# schema.net
KiCad netlist of a schematic drawn in EAGLE
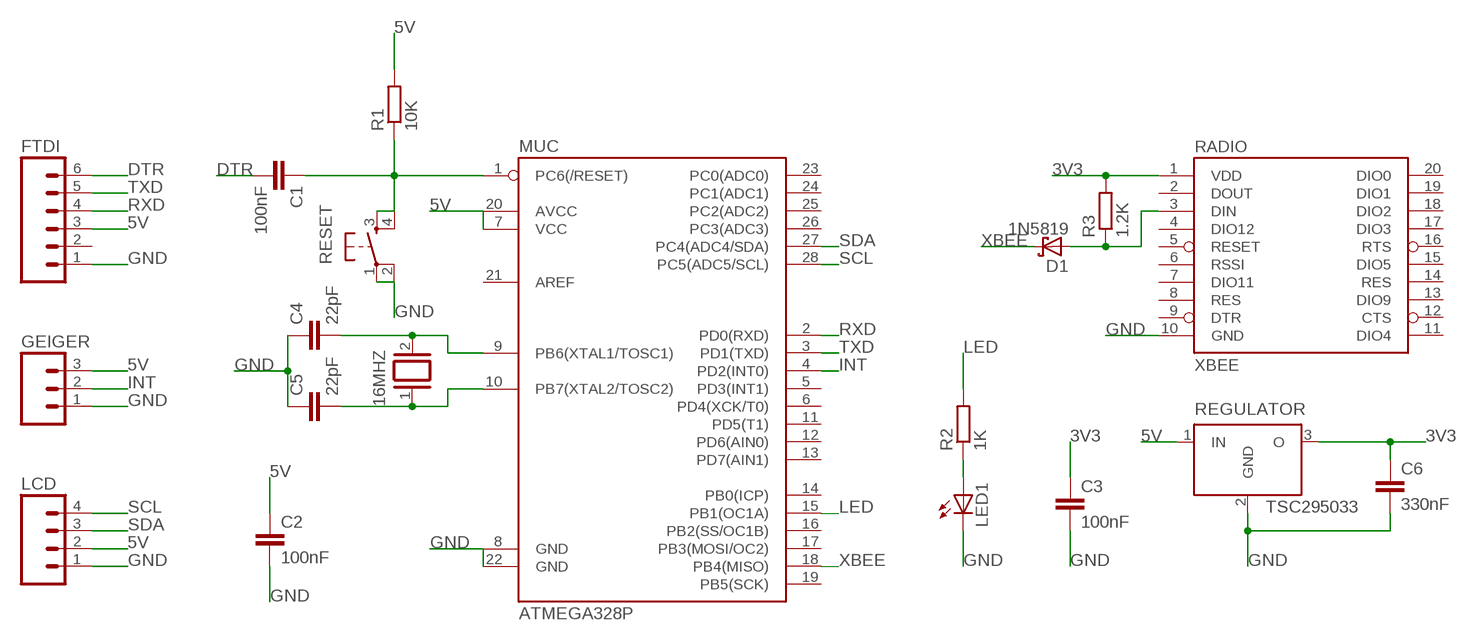
[diagram p0: schematic, sheet 1]

(export (version "E")
  (design (tool "Eeschema 10.0.6"))
  (components
    (comp (ref "16MHZ")
      (value "XTAL/S")
      (footprint "eagle-import:QS")
      (libsource (lib "eagle-import") (part "XTAL/S"))
    )
    (comp (ref "C1")
      (value "100nF")
      (footprint "eagle-import:C025-025X050")
      (libsource (lib "eagle-import") (part "C-EU025-025X050"))
    )
    (comp (ref "C2")
      (value "100nF")
      (footprint "eagle-import:C025-025X050")
      (libsource (lib "eagle-import") (part "C-EU025-025X050"))
    )
    (comp (ref "C3")
      (value "100nF")
      (footprint "eagle-import:C025-025X050")
      (libsource (lib "eagle-import") (part "C-EU025-025X050"))
    )
    (comp (ref "C4")
      (value "22pF")
      (footprint "eagle-import:C025-025X050")
      (libsource (lib "eagle-import") (part "C-EU025-025X050"))
    )
    (comp (ref "C5")
      (value "22pF")
      (footprint "eagle-import:C025-025X050")
      (libsource (lib "eagle-import") (part "C-EU025-025X050"))
    )
    (comp (ref "C6")
      (value "330nF")
      (footprint "eagle-import:C025-025X050")
      (libsource (lib "eagle-import") (part "C-EU025-025X050"))
    )
    (comp (ref "D1")
      (value "1N5819")
      (footprint "eagle-import:DO41-7.6")
      (libsource (lib "eagle-import") (part "1N5819-B"))
    )
    (comp (ref "FTDI")
      (value "M06SIP")
      (footprint "eagle-import:1X06")
      (libsource (lib "eagle-import") (part "M06SIP"))
    )
    (comp (ref "GEIGER")
      (value "M03PTH")
      (footprint "eagle-import:1X03")
      (libsource (lib "eagle-import") (part "M03PTH"))
    )
    (comp (ref "LCD")
      (value "M04PTH")
      (footprint "eagle-import:1X04")
      (libsource (lib "eagle-import") (part "M04PTH"))
    )
    (comp (ref "LED1")
      (value "LED3MM")
      (footprint "eagle-import:LED3MM")
      (libsource (lib "eagle-import") (part "LED3MM"))
    )
    (comp (ref "MUC")
      (value "ATMEGA328P")
      (footprint "eagle-import:DIL28-3")
      (libsource (lib "eagle-import") (part "ATMEGA328P_PDIP"))
    )
    (comp (ref "R1")
      (value "10K")
      (footprint "eagle-import:0207_10")
      (libsource (lib "eagle-import") (part "R-EU_0207/10"))
    )
    (comp (ref "R2")
      (value "1K")
      (footprint "eagle-import:0207_10")
      (libsource (lib "eagle-import") (part "R-EU_0207/10"))
    )
    (comp (ref "R3")
      (value "1.2K")
      (footprint "eagle-import:0207_10")
      (libsource (lib "eagle-import") (part "R-EU_0207/10"))
    )
    (comp (ref "RADIO")
      (value "XBEE")
      (footprint "eagle-import:XBEE-1")
      (libsource (lib "eagle-import") (part "XBEE-1B1"))
    )
    (comp (ref "REGULATOR")
      (value "TSC295033")
      (footprint "eagle-import:TO92")
      (fields (field (name "MF") "NATIONAL SEMICONDUCTOR") (field (name "MPN") "LP2950CZ-5.0/NOPB"))
      (libsource (lib "eagle-import") (part "LP2950Z"))
    )
    (comp (ref "RESET")
      (value "TAC_SWITCHPTH")
      (footprint "eagle-import:TACTILE-PTH")
      (libsource (lib "eagle-import") (part "TAC_SWITCHPTH"))
    )
  )
  (nets
    (net (code "1") (name "/3V3") (class "Default")
      (node (ref "C3") (pin "1") (pinfunction "1_1") (pintype "passive"))
      (node (ref "C6") (pin "1") (pinfunction "1_1") (pintype "passive"))
      (node (ref "R3") (pin "2") (pinfunction "2_2") (pintype "passive"))
      (node (ref "RADIO") (pin "1") (pinfunction "VDD_1") (pintype "power_in"))
      (node (ref "REGULATOR") (pin "3") (pinfunction "O_3") (pintype "output"))
    )
    (net (code "2") (name "/5V") (class "Default")
      (node (ref "C2") (pin "1") (pinfunction "1_1") (pintype "passive"))
      (node (ref "FTDI") (pin "3") (pinfunction "3_3") (pintype "passive"))
      (node (ref "GEIGER") (pin "3") (pinfunction "3_3") (pintype "passive"))
      (node (ref "LCD") (pin "2") (pinfunction "2_2") (pintype "passive"))
      (node (ref "MUC") (pin "20") (pinfunction "AVCC_20") (pintype "bidirectional"))
      (node (ref "MUC") (pin "7") (pinfunction "VCC_7") (pintype "bidirectional"))
      (node (ref "R1") (pin "2") (pinfunction "2_2") (pintype "passive"))
      (node (ref "REGULATOR") (pin "1") (pinfunction "IN_1") (pintype "input"))
    )
    (net (code "3") (name "/DTR") (class "Default")
      (node (ref "C1") (pin "2") (pinfunction "2_2") (pintype "passive"))
      (node (ref "FTDI") (pin "6") (pinfunction "6_6") (pintype "passive"))
    )
    (net (code "4") (name "/GND") (class "Default")
      (node (ref "C2") (pin "2") (pinfunction "2_2") (pintype "passive"))
      (node (ref "C3") (pin "2") (pinfunction "2_2") (pintype "passive"))
      (node (ref "C4") (pin "1") (pinfunction "1_1") (pintype "passive"))
      (node (ref "C5") (pin "1") (pinfunction "1_1") (pintype "passive"))
      (node (ref "C6") (pin "2") (pinfunction "2_2") (pintype "passive"))
      (node (ref "FTDI") (pin "1") (pinfunction "1_1") (pintype "passive"))
      (node (ref "GEIGER") (pin "1") (pinfunction "1_1") (pintype "passive"))
      (node (ref "LCD") (pin "1") (pinfunction "1_1") (pintype "passive"))
      (node (ref "LED1") (pin "K") (pinfunction "C_K") (pintype "passive"))
      (node (ref "MUC") (pin "22") (pinfunction "GND_22") (pintype "bidirectional"))
      (node (ref "MUC") (pin "8") (pinfunction "GND_8") (pintype "bidirectional"))
      (node (ref "RADIO") (pin "10") (pinfunction "GND_10") (pintype "power_in"))
      (node (ref "REGULATOR") (pin "2") (pinfunction "GND_2") (pintype "power_in"))
      (node (ref "RESET") (pin "1") (pinfunction "1_1") (pintype "passive"))
      (node (ref "RESET") (pin "2") (pinfunction "2_2") (pintype "passive"))
    )
    (net (code "5") (name "/INT") (class "Default")
      (node (ref "GEIGER") (pin "2") (pinfunction "2_2") (pintype "passive"))
      (node (ref "MUC") (pin "4") (pinfunction "PD2(INT0)_4") (pintype "bidirectional"))
    )
    (net (code "6") (name "/LED") (class "Default")
      (node (ref "MUC") (pin "15") (pinfunction "PB1(OC1A)_15") (pintype "bidirectional"))
      (node (ref "R2") (pin "2") (pinfunction "2_2") (pintype "passive"))
    )
    (net (code "7") (name "/RXD") (class "Default")
      (node (ref "FTDI") (pin "4") (pinfunction "4_4") (pintype "passive"))
      (node (ref "MUC") (pin "2") (pinfunction "PD0(RXD)_2") (pintype "bidirectional"))
    )
    (net (code "8") (name "/SCL") (class "Default")
      (node (ref "LCD") (pin "4") (pinfunction "4_4") (pintype "passive"))
      (node (ref "MUC") (pin "28") (pinfunction "PC5(ADC5/SCL)_28") (pintype "bidirectional"))
    )
    (net (code "9") (name "/SDA") (class "Default")
      (node (ref "LCD") (pin "3") (pinfunction "3_3") (pintype "passive"))
      (node (ref "MUC") (pin "27") (pinfunction "PC4(ADC4/SDA)_27") (pintype "bidirectional"))
    )
    (net (code "10") (name "/TXD") (class "Default")
      (node (ref "FTDI") (pin "5") (pinfunction "5_5") (pintype "passive"))
      (node (ref "MUC") (pin "3") (pinfunction "PD1(TXD)_3") (pintype "bidirectional"))
    )
    (net (code "11") (name "/XBEE") (class "Default")
      (node (ref "D1") (pin "C") (pinfunction "C_C") (pintype "passive"))
      (node (ref "MUC") (pin "18") (pinfunction "PB4(MISO)_18") (pintype "bidirectional"))
    )
    (net (code "12") (name "Net-(LED1-PadA)") (class "Default")
      (node (ref "LED1") (pin "A") (pinfunction "A_A") (pintype "passive"))
      (node (ref "R2") (pin "1") (pinfunction "1_1") (pintype "passive"))
    )
    (net (code "13") (name "Net-(MUC-PB6(XTAL1{slash}TOSC1))") (class "Default")
      (node (ref "16MHZ") (pin "2") (pinfunction "2_2") (pintype "passive"))
      (node (ref "C4") (pin "2") (pinfunction "2_2") (pintype "passive"))
      (node (ref "MUC") (pin "9") (pinfunction "PB6(XTAL1/TOSC1)_9") (pintype "bidirectional"))
    )
    (net (code "14") (name "Net-(MUC-PB7(XTAL2{slash}TOSC2))") (class "Default")
      (node (ref "16MHZ") (pin "1") (pinfunction "1_1") (pintype "passive"))
      (node (ref "C5") (pin "2") (pinfunction "2_2") (pintype "passive"))
      (node (ref "MUC") (pin "10") (pinfunction "PB7(XTAL2/TOSC2)_10") (pintype "bidirectional"))
    )
    (net (code "15") (name "Net-(MUC-PC6({slash}RESET))") (class "Default")
      (node (ref "C1") (pin "1") (pinfunction "1_1") (pintype "passive"))
      (node (ref "MUC") (pin "1") (pinfunction "PC6(/RESET)_1") (pintype "bidirectional"))
      (node (ref "R1") (pin "1") (pinfunction "1_1") (pintype "passive"))
      (node (ref "RESET") (pin "3") (pinfunction "3_3") (pintype "passive"))
      (node (ref "RESET") (pin "4") (pinfunction "4_4") (pintype "passive"))
    )
    (net (code "16") (name "Net-(RADIO-DIN)") (class "Default")
      (node (ref "D1") (pin "A") (pinfunction "A_A") (pintype "passive"))
      (node (ref "R3") (pin "1") (pinfunction "1_1") (pintype "passive"))
      (node (ref "RADIO") (pin "3") (pinfunction "DIN_3") (pintype "input"))
    )
    (net (code "17") (name "unconnected-(FTDI-Pad2)") (class "Default")
      (node (ref "FTDI") (pin "2") (pinfunction "2_2") (pintype "passive"))
    )
    (net (code "18") (name "unconnected-(MUC-AREF-Pad21)") (class "Default")
      (node (ref "MUC") (pin "21") (pinfunction "AREF_21") (pintype "bidirectional"))
    )
    (net (code "19") (name "unconnected-(MUC-PB0(ICP)-Pad14)") (class "Default")
      (node (ref "MUC") (pin "14") (pinfunction "PB0(ICP)_14") (pintype "bidirectional"))
    )
    (net (code "20") (name "unconnected-(MUC-PB2(SS{slash}OC1B)-Pad16)") (class "Default")
      (node (ref "MUC") (pin "16") (pinfunction "PB2(SS/OC1B)_16") (pintype "bidirectional"))
    )
    (net (code "21") (name "unconnected-(MUC-PB3(MOSI{slash}OC2)-Pad17)") (class "Default")
      (node (ref "MUC") (pin "17") (pinfunction "PB3(MOSI/OC2)_17") (pintype "bidirectional"))
    )
    (net (code "22") (name "unconnected-(MUC-PB5(SCK)-Pad19)") (class "Default")
      (node (ref "MUC") (pin "19") (pinfunction "PB5(SCK)_19") (pintype "bidirectional"))
    )
    (net (code "23") (name "unconnected-(MUC-PC0(ADC0)-Pad23)") (class "Default")
      (node (ref "MUC") (pin "23") (pinfunction "PC0(ADC0)_23") (pintype "bidirectional"))
    )
    (net (code "24") (name "unconnected-(MUC-PC1(ADC1)-Pad24)") (class "Default")
      (node (ref "MUC") (pin "24") (pinfunction "PC1(ADC1)_24") (pintype "bidirectional"))
    )
    (net (code "25") (name "unconnected-(MUC-PC2(ADC2)-Pad25)") (class "Default")
      (node (ref "MUC") (pin "25") (pinfunction "PC2(ADC2)_25") (pintype "bidirectional"))
    )
    (net (code "26") (name "unconnected-(MUC-PC3(ADC3)-Pad26)") (class "Default")
      (node (ref "MUC") (pin "26") (pinfunction "PC3(ADC3)_26") (pintype "bidirectional"))
    )
    (net (code "27") (name "unconnected-(MUC-PD3(INT1)-Pad5)") (class "Default")
      (node (ref "MUC") (pin "5") (pinfunction "PD3(INT1)_5") (pintype "bidirectional"))
    )
    (net (code "28") (name "unconnected-(MUC-PD4(XCK{slash}T0)-Pad6)") (class "Default")
      (node (ref "MUC") (pin "6") (pinfunction "PD4(XCK/T0)_6") (pintype "bidirectional"))
    )
    (net (code "29") (name "unconnected-(MUC-PD5(T1)-Pad11)") (class "Default")
      (node (ref "MUC") (pin "11") (pinfunction "PD5(T1)_11") (pintype "bidirectional"))
    )
    (net (code "30") (name "unconnected-(MUC-PD6(AIN0)-Pad12)") (class "Default")
      (node (ref "MUC") (pin "12") (pinfunction "PD6(AIN0)_12") (pintype "bidirectional"))
    )
    (net (code "31") (name "unconnected-(MUC-PD7(AIN1)-Pad13)") (class "Default")
      (node (ref "MUC") (pin "13") (pinfunction "PD7(AIN1)_13") (pintype "bidirectional"))
    )
    (net (code "32") (name "unconnected-(RADIO-CTS-Pad12)") (class "Default")
      (node (ref "RADIO") (pin "12") (pinfunction "CTS_12") (pintype "output"))
    )
    (net (code "33") (name "unconnected-(RADIO-DIO0-Pad20)") (class "Default")
      (node (ref "RADIO") (pin "20") (pinfunction "DIO0_20") (pintype "bidirectional"))
    )
    (net (code "34") (name "unconnected-(RADIO-DIO1-Pad19)") (class "Default")
      (node (ref "RADIO") (pin "19") (pinfunction "DIO1_19") (pintype "bidirectional"))
    )
    (net (code "35") (name "unconnected-(RADIO-DIO2-Pad18)") (class "Default")
      (node (ref "RADIO") (pin "18") (pinfunction "DIO2_18") (pintype "bidirectional"))
    )
    (net (code "36") (name "unconnected-(RADIO-DIO3-Pad17)") (class "Default")
      (node (ref "RADIO") (pin "17") (pinfunction "DIO3_17") (pintype "bidirectional"))
    )
    (net (code "37") (name "unconnected-(RADIO-DIO4-Pad11)") (class "Default")
      (node (ref "RADIO") (pin "11") (pinfunction "DIO4_11") (pintype "bidirectional"))
    )
    (net (code "38") (name "unconnected-(RADIO-DIO5-Pad15)") (class "Default")
      (node (ref "RADIO") (pin "15") (pinfunction "DIO5_15") (pintype "bidirectional"))
    )
    (net (code "39") (name "unconnected-(RADIO-DIO9-Pad13)") (class "Default")
      (node (ref "RADIO") (pin "13") (pinfunction "DIO9_13") (pintype "bidirectional"))
    )
    (net (code "40") (name "unconnected-(RADIO-DIO11-Pad7)") (class "Default")
      (node (ref "RADIO") (pin "7") (pinfunction "DIO11_7") (pintype "bidirectional"))
    )
    (net (code "41") (name "unconnected-(RADIO-DIO12-Pad4)") (class "Default")
      (node (ref "RADIO") (pin "4") (pinfunction "DIO12_4") (pintype "bidirectional"))
    )
    (net (code "42") (name "unconnected-(RADIO-DOUT-Pad2)") (class "Default")
      (node (ref "RADIO") (pin "2") (pinfunction "DOUT_2") (pintype "output"))
    )
    (net (code "43") (name "unconnected-(RADIO-DTR-Pad9)") (class "Default")
      (node (ref "RADIO") (pin "9") (pinfunction "DTR_9") (pintype "bidirectional"))
    )
    (net (code "44") (name "unconnected-(RADIO-RES-Pad8)") (class "Default")
      (node (ref "RADIO") (pin "8") (pinfunction "RES_8") (pintype "bidirectional"))
    )
    (net (code "45") (name "unconnected-(RADIO-RES-Pad14)") (class "Default")
      (node (ref "RADIO") (pin "14") (pinfunction "RES_14") (pintype "bidirectional"))
    )
    (net (code "46") (name "unconnected-(RADIO-RESET-Pad5)") (class "Default")
      (node (ref "RADIO") (pin "5") (pinfunction "RESET_5") (pintype "input"))
    )
    (net (code "47") (name "unconnected-(RADIO-RSSI-Pad6)") (class "Default")
      (node (ref "RADIO") (pin "6") (pinfunction "RSSI_6") (pintype "bidirectional"))
    )
    (net (code "48") (name "unconnected-(RADIO-RTS-Pad16)") (class "Default")
      (node (ref "RADIO") (pin "16") (pinfunction "RTS_16") (pintype "input"))
    )
  )
)
